# Sheet_1_2024-08-14.net
KiCad netlist of a schematic drawn in Altium Designer
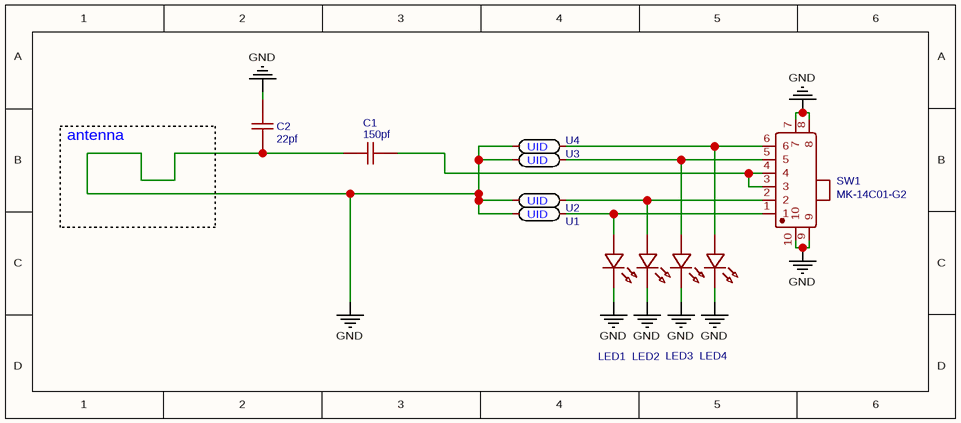
[diagram p0: Sheet_1_2024-08-14.schdoc]

(export (version "E")
  (design (tool "Eeschema 10.0.6"))
  (components
    (comp (ref "C1")
      (value "150pf")
      (fields
        (field (name "MANUFACTURER") "TORCH(火炬)")
        (field (name "MANUFACTURER PART") "C0402B103K500NT")
        (field (name "CONTRIBUTOR") "lcsc")
      )
      (libsource (lib "altium-import") (part "root_0_150pf_"))
    )
    (comp (ref "C2")
      (value "22pf")
      (fields
        (field (name "MANUFACTURER") "TORCH(火炬)")
        (field (name "MANUFACTURER PART") "C0402B103K500NT")
        (field (name "CONTRIBUTOR") "lcsc")
      )
      (libsource (lib "altium-import") (part "root_1_22pf_"))
    )
    (comp (ref "LED1")
      (value "LED-0603_G")
      (fields
        (field (name "MANUFACTURER") "EVERLIGHT(台湾亿光)")
        (field (name "MANUFACTURER PART") "19-217/GHC-YR1S2/3T")
        (field (name "CONTRIBUTOR") "LCEDA_Lib")
      )
      (libsource (lib "altium-import") (part "root_3_LED-0603_G_"))
    )
    (comp (ref "LED2")
      (value "LED-0603_G")
      (fields
        (field (name "MANUFACTURER") "EVERLIGHT(台湾亿光)")
        (field (name "MANUFACTURER PART") "19-217/GHC-YR1S2/3T")
        (field (name "CONTRIBUTOR") "LCEDA_Lib")
      )
      (libsource (lib "altium-import") (part "root_3_LED-0603_G_"))
    )
    (comp (ref "LED3")
      (value "LED-0603_G")
      (fields
        (field (name "MANUFACTURER") "EVERLIGHT(台湾亿光)")
        (field (name "MANUFACTURER PART") "19-217/GHC-YR1S2/3T")
        (field (name "CONTRIBUTOR") "LCEDA_Lib")
      )
      (libsource (lib "altium-import") (part "root_3_LED-0603_G_"))
    )
    (comp (ref "LED4")
      (value "LED-0603_G")
      (fields
        (field (name "MANUFACTURER") "EVERLIGHT(台湾亿光)")
        (field (name "MANUFACTURER PART") "19-217/GHC-YR1S2/3T")
        (field (name "CONTRIBUTOR") "LCEDA_Lib")
      )
      (libsource (lib "altium-import") (part "root_3_LED-0603_G_"))
    )
    (comp (ref "SW1")
      (value "MK-14C01-G2")
      (fields (field (name "MANUFACTURER") "DEALON(德艺隆)") (field (name "CONTRIBUTOR") "LCSC"))
      (libsource (lib "altium-import") (part "root_1_MK-14C01-G2_"))
    )
    (comp (ref "U1")
      (value "NFC-CUID-COB")
      (fields (field (name "CONTRIBUTOR") "OTTER"))
      (libsource (lib "altium-import") (part "root_2_NFC-CUID-COB_"))
    )
    (comp (ref "U2")
      (value "NFC-CUID-COB")
      (fields (field (name "CONTRIBUTOR") "OTTER"))
      (libsource (lib "altium-import") (part "root_2_NFC-CUID-COB_"))
    )
    (comp (ref "U3")
      (value "NFC-CUID-COB")
      (fields (field (name "CONTRIBUTOR") "OTTER"))
      (libsource (lib "altium-import") (part "root_2_NFC-CUID-COB_"))
    )
    (comp (ref "U4")
      (value "NFC-CUID-COB")
      (fields (field (name "CONTRIBUTOR") "OTTER"))
      (libsource (lib "altium-import") (part "root_2_NFC-CUID-COB_"))
    )
  )
  (nets
    (net (code "1") (name "GND") (class "Default")
      (node (ref "C1") (pin "1") (pinfunction "1_1") (pintype "passive"))
      (node (ref "C2") (pin "1") (pinfunction "1_1") (pintype "passive"))
      (node (ref "C2") (pin "2") (pinfunction "2_2") (pintype "passive"))
      (node (ref "LED1") (pin "2") (pinfunction "2_2") (pintype "passive"))
      (node (ref "LED2") (pin "2") (pinfunction "2_2") (pintype "passive"))
      (node (ref "LED3") (pin "2") (pinfunction "2_2") (pintype "passive"))
      (node (ref "LED4") (pin "2") (pinfunction "2_2") (pintype "passive"))
      (node (ref "SW1") (pin "10") (pinfunction "10_10") (pintype "passive"))
      (node (ref "SW1") (pin "7") (pinfunction "7_7") (pintype "passive"))
      (node (ref "SW1") (pin "8") (pinfunction "8_8") (pintype "passive"))
      (node (ref "SW1") (pin "9") (pinfunction "9_9") (pintype "passive"))
      (node (ref "U1") (pin "2") (pinfunction "2_2") (pintype "passive"))
      (node (ref "U2") (pin "2") (pinfunction "2_2") (pintype "passive"))
      (node (ref "U3") (pin "2") (pinfunction "2_2") (pintype "passive"))
      (node (ref "U4") (pin "2") (pinfunction "2_2") (pintype "passive"))
    )
    (net (code "2") (name "Net-(C1-Pad2)") (class "Default")
      (node (ref "C1") (pin "2") (pinfunction "2_2") (pintype "passive"))
      (node (ref "SW1") (pin "3") (pinfunction "3_3") (pintype "passive"))
      (node (ref "SW1") (pin "4") (pinfunction "4_4") (pintype "passive"))
    )
    (net (code "3") (name "Net-(LED1-Pad1)") (class "Default")
      (node (ref "LED1") (pin "1") (pinfunction "1_1") (pintype "passive"))
      (node (ref "SW1") (pin "1") (pinfunction "1_1") (pintype "passive"))
      (node (ref "U1") (pin "1") (pinfunction "1_1") (pintype "passive"))
    )
    (net (code "4") (name "Net-(LED2-Pad1)") (class "Default")
      (node (ref "LED2") (pin "1") (pinfunction "1_1") (pintype "passive"))
      (node (ref "SW1") (pin "2") (pinfunction "2_2") (pintype "passive"))
      (node (ref "U2") (pin "1") (pinfunction "1_1") (pintype "passive"))
    )
    (net (code "5") (name "Net-(LED3-Pad1)") (class "Default")
      (node (ref "LED3") (pin "1") (pinfunction "1_1") (pintype "passive"))
      (node (ref "SW1") (pin "5") (pinfunction "5_5") (pintype "passive"))
      (node (ref "U3") (pin "1") (pinfunction "1_1") (pintype "passive"))
    )
    (net (code "6") (name "Net-(LED4-Pad1)") (class "Default")
      (node (ref "LED4") (pin "1") (pinfunction "1_1") (pintype "passive"))
      (node (ref "SW1") (pin "6") (pinfunction "6_6") (pintype "passive"))
      (node (ref "U4") (pin "1") (pinfunction "1_1") (pintype "passive"))
    )
  )
)
